# indication.net
KiCad netlist of a schematic drawn in EAGLE
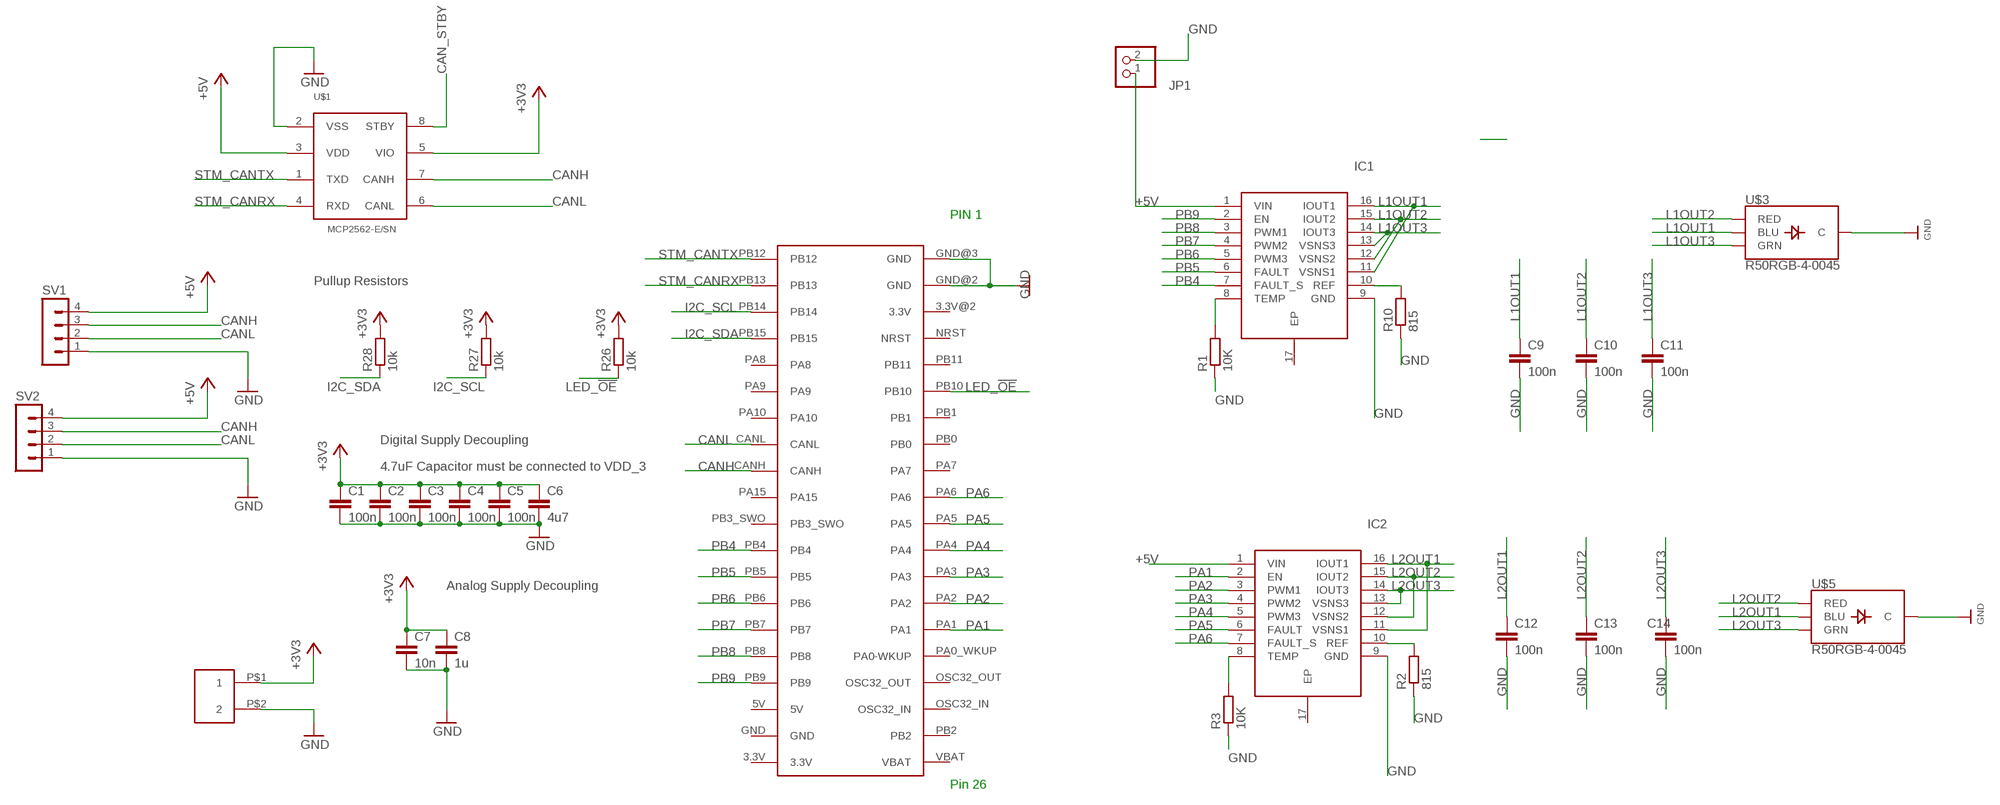
[diagram p0: schematic, sheet 1]

(export (version "E")
  (design (tool "Eeschema 10.0.6"))
  (components
    (comp (ref "C1")
      (value "100n")
      (footprint "eagle-import:C0805")
      (libsource (lib "eagle-import") (part "resistor_348_C-EUC0805"))
    )
    (comp (ref "C2")
      (value "100n")
      (footprint "eagle-import:C0805")
      (libsource (lib "eagle-import") (part "resistor_348_C-EUC0805"))
    )
    (comp (ref "C3")
      (value "100n")
      (footprint "eagle-import:C0805")
      (libsource (lib "eagle-import") (part "resistor_348_C-EUC0805"))
    )
    (comp (ref "C4")
      (value "100n")
      (footprint "eagle-import:C0805")
      (libsource (lib "eagle-import") (part "resistor_348_C-EUC0805"))
    )
    (comp (ref "C5")
      (value "100n")
      (footprint "eagle-import:C0805")
      (libsource (lib "eagle-import") (part "resistor_348_C-EUC0805"))
    )
    (comp (ref "C6")
      (value "4u7")
      (footprint "eagle-import:C0805")
      (libsource (lib "eagle-import") (part "resistor_348_C-EUC0805"))
    )
    (comp (ref "C7")
      (value "10n")
      (footprint "eagle-import:C0805")
      (libsource (lib "eagle-import") (part "resistor_348_C-EUC0805"))
    )
    (comp (ref "C8")
      (value "1u")
      (footprint "eagle-import:C0805")
      (libsource (lib "eagle-import") (part "resistor_348_C-EUC0805"))
    )
    (comp (ref "C9")
      (value "100n")
      (footprint "eagle-import:C0805")
      (libsource (lib "eagle-import") (part "C-EUC0805"))
    )
    (comp (ref "C10")
      (value "100n")
      (footprint "eagle-import:C0805")
      (libsource (lib "eagle-import") (part "C-EUC0805"))
    )
    (comp (ref "C11")
      (value "100n")
      (footprint "eagle-import:C0805")
      (libsource (lib "eagle-import") (part "C-EUC0805"))
    )
    (comp (ref "C12")
      (value "100n")
      (footprint "eagle-import:C0805")
      (libsource (lib "eagle-import") (part "C-EUC0805"))
    )
    (comp (ref "C13")
      (value "100n")
      (footprint "eagle-import:C0805")
      (libsource (lib "eagle-import") (part "C-EUC0805"))
    )
    (comp (ref "C14")
      (value "100n")
      (footprint "eagle-import:C0805")
      (libsource (lib "eagle-import") (part "C-EUC0805"))
    )
    (comp (ref "IC1")
      (value "TPS92630QPWPRQ1")
      (footprint "eagle-import:SOP65P640X120-17N")
      (fields (field (name "MOUSER_PART_NUMBER") "595-TPS92630QPWPRQ1"))
      (libsource (lib "eagle-import") (part "TPS92630QPWPRQ1"))
    )
    (comp (ref "IC2")
      (value "TPS92630QPWPRQ1")
      (footprint "eagle-import:SOP65P640X120-17N")
      (fields (field (name "MOUSER_PART_NUMBER") "595-TPS92630QPWPRQ1"))
      (libsource (lib "eagle-import") (part "TPS92630QPWPRQ1"))
    )
    (comp (ref "JP1")
      (value "PINHD-1X2")
      (footprint "eagle-import:1X02")
      (libsource (lib "eagle-import") (part "PINHD-1X2"))
    )
    (comp (ref "R1")
      (value "10K")
      (footprint "eagle-import:R0805")
      (libsource (lib "eagle-import") (part "R-EU_R0805"))
    )
    (comp (ref "R2")
      (value "815")
      (footprint "eagle-import:R0805")
      (libsource (lib "eagle-import") (part "R-EU_R0805"))
    )
    (comp (ref "R3")
      (value "10K")
      (footprint "eagle-import:R0805")
      (libsource (lib "eagle-import") (part "R-EU_R0805"))
    )
    (comp (ref "R10")
      (value "815")
      (footprint "eagle-import:R0805")
      (libsource (lib "eagle-import") (part "R-EU_R0805"))
    )
    (comp (ref "R26")
      (value "10k")
      (footprint "eagle-import:R0805")
      (libsource (lib "eagle-import") (part "R-EU_R0805"))
    )
    (comp (ref "R27")
      (value "10k")
      (footprint "eagle-import:R0805")
      (libsource (lib "eagle-import") (part "R-EU_R0805"))
    )
    (comp (ref "R28")
      (value "10k")
      (footprint "eagle-import:R0805")
      (libsource (lib "eagle-import") (part "R-EU_R0805"))
    )
    (comp (ref "SV1")
      (value "MA04-1")
      (footprint "eagle-import:MA04-1")
      (libsource (lib "eagle-import") (part "MA04-1"))
    )
    (comp (ref "SV2")
      (value "MA04-1")
      (footprint "eagle-import:MA04-1")
      (libsource (lib "eagle-import") (part "MA04-1"))
    )
    (comp (ref "U$1")
      (value "MCP2562-E/SN")
      (footprint "eagle-import:SOIC8")
      (libsource (lib "eagle-import") (part "MCP2562-E/SN"))
    )
    (comp (ref "U$2")
      (value "STM-DEV-BOARD")
      (footprint "eagle-import:STM-DEV-BOARD")
      (libsource (lib "eagle-import") (part "STM-DEV-BOARD"))
    )
    (comp (ref "U$3")
      (value "R50RGB-4-0045")
      (footprint "eagle-import:R50RGB-4-0045")
      (libsource (lib "eagle-import") (part "R50RGB-4-0045"))
    )
    (comp (ref "U$4")
      (value "TE-CONN_5-103669-1")
      (footprint "eagle-import:TE-CONN_5-103669-1")
      (libsource (lib "eagle-import") (part "TE-CONN_5-103669-1"))
    )
    (comp (ref "U$5")
      (value "R50RGB-4-0045")
      (footprint "eagle-import:R50RGB-4-0045")
      (libsource (lib "eagle-import") (part "R50RGB-4-0045"))
    )
  )
  (nets
    (net (code "1") (name "+3V3") (class "Default")
      (node (ref "C1") (pin "1") (pinfunction "1_1") (pintype "passive"))
      (node (ref "C2") (pin "1") (pinfunction "1_1") (pintype "passive"))
      (node (ref "C3") (pin "1") (pinfunction "1_1") (pintype "passive"))
      (node (ref "C4") (pin "1") (pinfunction "1_1") (pintype "passive"))
      (node (ref "C5") (pin "1") (pinfunction "1_1") (pintype "passive"))
      (node (ref "C6") (pin "1") (pinfunction "1_1") (pintype "passive"))
      (node (ref "C7") (pin "1") (pinfunction "1_1") (pintype "passive"))
      (node (ref "C8") (pin "1") (pinfunction "1_1") (pintype "passive"))
      (node (ref "R26") (pin "2") (pinfunction "2_2") (pintype "passive"))
      (node (ref "R27") (pin "2") (pinfunction "2_2") (pintype "passive"))
      (node (ref "R28") (pin "2") (pinfunction "2_2") (pintype "passive"))
      (node (ref "U$1") (pin "5") (pinfunction "VIO_5") (pintype "bidirectional"))
      (node (ref "U$4") (pin "P$1") (pinfunction "1_P$1") (pintype "bidirectional"))
    )
    (net (code "2") (name "+5V") (class "Default")
      (node (ref "IC1") (pin "1") (pinfunction "VIN_1") (pintype "bidirectional"))
      (node (ref "IC2") (pin "1") (pinfunction "VIN_1") (pintype "bidirectional"))
      (node (ref "JP1") (pin "1") (pinfunction "1_1") (pintype "passive"))
      (node (ref "SV1") (pin "4") (pinfunction "4_4") (pintype "passive"))
      (node (ref "SV2") (pin "4") (pinfunction "4_4") (pintype "passive"))
      (node (ref "U$1") (pin "3") (pinfunction "VDD_3") (pintype "bidirectional"))
    )
    (net (code "3") (name "/CANH") (class "Default")
      (node (ref "SV1") (pin "3") (pinfunction "3_3") (pintype "passive"))
      (node (ref "SV2") (pin "3") (pinfunction "3_3") (pintype "passive"))
      (node (ref "U$1") (pin "7") (pinfunction "CANH_7") (pintype "bidirectional"))
      (node (ref "U$2") (pin "CANH") (pinfunction "CANH_CANH") (pintype "bidirectional"))
    )
    (net (code "4") (name "/CANL") (class "Default")
      (node (ref "SV1") (pin "2") (pinfunction "2_2") (pintype "passive"))
      (node (ref "SV2") (pin "2") (pinfunction "2_2") (pintype "passive"))
      (node (ref "U$1") (pin "6") (pinfunction "CANL_6") (pintype "bidirectional"))
      (node (ref "U$2") (pin "CANL") (pinfunction "CANL_CANL") (pintype "bidirectional"))
    )
    (net (code "5") (name "/CAN_STBY") (class "Default")
      (node (ref "U$1") (pin "8") (pinfunction "STBY_8") (pintype "bidirectional"))
    )
    (net (code "6") (name "/I2C_SCL") (class "Default")
      (node (ref "R27") (pin "1") (pinfunction "1_1") (pintype "passive"))
      (node (ref "U$2") (pin "PB14") (pinfunction "PB14_PB14") (pintype "bidirectional"))
    )
    (net (code "7") (name "/I2C_SDA") (class "Default")
      (node (ref "R28") (pin "1") (pinfunction "1_1") (pintype "passive"))
      (node (ref "U$2") (pin "PB15") (pinfunction "PB15_PB15") (pintype "bidirectional"))
    )
    (net (code "8") (name "/L1OUT1") (class "Default")
      (node (ref "C9") (pin "1") (pinfunction "1_1") (pintype "passive"))
      (node (ref "IC1") (pin "11") (pinfunction "VSNS1_11") (pintype "bidirectional"))
      (node (ref "IC1") (pin "16") (pinfunction "IOUT1_16") (pintype "bidirectional"))
      (node (ref "U$3") (pin "P$3") (pinfunction "BLU_P$3") (pintype "bidirectional"))
    )
    (net (code "9") (name "/L1OUT2") (class "Default")
      (node (ref "C10") (pin "1") (pinfunction "1_1") (pintype "passive"))
      (node (ref "IC1") (pin "12") (pinfunction "VSNS2_12") (pintype "bidirectional"))
      (node (ref "IC1") (pin "15") (pinfunction "IOUT2_15") (pintype "bidirectional"))
      (node (ref "U$3") (pin "P$4") (pinfunction "RED_P$4") (pintype "bidirectional"))
    )
    (net (code "10") (name "/L1OUT3") (class "Default")
      (node (ref "C11") (pin "1") (pinfunction "1_1") (pintype "passive"))
      (node (ref "IC1") (pin "13") (pinfunction "VSNS3_13") (pintype "bidirectional"))
      (node (ref "IC1") (pin "14") (pinfunction "IOUT3_14") (pintype "bidirectional"))
      (node (ref "U$3") (pin "P$1") (pinfunction "GRN_P$1") (pintype "bidirectional"))
    )
    (net (code "11") (name "/L2OUT1") (class "Default")
      (node (ref "C12") (pin "1") (pinfunction "1_1") (pintype "passive"))
      (node (ref "IC2") (pin "11") (pinfunction "VSNS1_11") (pintype "bidirectional"))
      (node (ref "IC2") (pin "16") (pinfunction "IOUT1_16") (pintype "bidirectional"))
      (node (ref "U$5") (pin "P$3") (pinfunction "BLU_P$3") (pintype "bidirectional"))
    )
    (net (code "12") (name "/L2OUT2") (class "Default")
      (node (ref "C13") (pin "1") (pinfunction "1_1") (pintype "passive"))
      (node (ref "IC2") (pin "12") (pinfunction "VSNS2_12") (pintype "bidirectional"))
      (node (ref "IC2") (pin "15") (pinfunction "IOUT2_15") (pintype "bidirectional"))
      (node (ref "U$5") (pin "P$4") (pinfunction "RED_P$4") (pintype "bidirectional"))
    )
    (net (code "13") (name "/L2OUT3") (class "Default")
      (node (ref "C14") (pin "1") (pinfunction "1_1") (pintype "passive"))
      (node (ref "IC2") (pin "13") (pinfunction "VSNS3_13") (pintype "bidirectional"))
      (node (ref "IC2") (pin "14") (pinfunction "IOUT3_14") (pintype "bidirectional"))
      (node (ref "U$5") (pin "P$1") (pinfunction "GRN_P$1") (pintype "bidirectional"))
    )
    (net (code "14") (name "/LED_~{OE}") (class "Default")
      (node (ref "R26") (pin "1") (pinfunction "1_1") (pintype "passive"))
      (node (ref "U$2") (pin "PB10") (pinfunction "PB10_PB10") (pintype "bidirectional"))
    )
    (net (code "15") (name "/PA1") (class "Default")
      (node (ref "IC2") (pin "2") (pinfunction "EN_2") (pintype "bidirectional"))
      (node (ref "U$2") (pin "PA1") (pinfunction "PA1_PA1") (pintype "bidirectional"))
    )
    (net (code "16") (name "/PA2") (class "Default")
      (node (ref "IC2") (pin "3") (pinfunction "PWM1_3") (pintype "bidirectional"))
      (node (ref "U$2") (pin "PA2") (pinfunction "PA2_PA2") (pintype "bidirectional"))
    )
    (net (code "17") (name "/PA3") (class "Default")
      (node (ref "IC2") (pin "4") (pinfunction "PWM2_4") (pintype "bidirectional"))
      (node (ref "U$2") (pin "PA3") (pinfunction "PA3_PA3") (pintype "bidirectional"))
    )
    (net (code "18") (name "/PA4") (class "Default")
      (node (ref "IC2") (pin "5") (pinfunction "PWM3_5") (pintype "bidirectional"))
      (node (ref "U$2") (pin "PA4") (pinfunction "PA4_PA4") (pintype "bidirectional"))
    )
    (net (code "19") (name "/PA5") (class "Default")
      (node (ref "IC2") (pin "6") (pinfunction "FAULT_6") (pintype "bidirectional"))
      (node (ref "U$2") (pin "PA5") (pinfunction "PA5_PA5") (pintype "bidirectional"))
    )
    (net (code "20") (name "/PA6") (class "Default")
      (node (ref "IC2") (pin "7") (pinfunction "FAULT_S_7") (pintype "bidirectional"))
      (node (ref "U$2") (pin "PA6") (pinfunction "PA6_PA6") (pintype "bidirectional"))
    )
    (net (code "21") (name "/PB4") (class "Default")
      (node (ref "IC1") (pin "7") (pinfunction "FAULT_S_7") (pintype "bidirectional"))
      (node (ref "U$2") (pin "PB4") (pinfunction "PB4_PB4") (pintype "bidirectional"))
    )
    (net (code "22") (name "/PB5") (class "Default")
      (node (ref "IC1") (pin "6") (pinfunction "FAULT_6") (pintype "bidirectional"))
      (node (ref "U$2") (pin "PB5") (pinfunction "PB5_PB5") (pintype "bidirectional"))
    )
    (net (code "23") (name "/PB6") (class "Default")
      (node (ref "IC1") (pin "5") (pinfunction "PWM3_5") (pintype "bidirectional"))
      (node (ref "U$2") (pin "PB6") (pinfunction "PB6_PB6") (pintype "bidirectional"))
    )
    (net (code "24") (name "/PB7") (class "Default")
      (node (ref "IC1") (pin "4") (pinfunction "PWM2_4") (pintype "bidirectional"))
      (node (ref "U$2") (pin "PB7") (pinfunction "PB7_PB7") (pintype "bidirectional"))
    )
    (net (code "25") (name "/PB8") (class "Default")
      (node (ref "IC1") (pin "3") (pinfunction "PWM1_3") (pintype "bidirectional"))
      (node (ref "U$2") (pin "PB8") (pinfunction "PB8_PB8") (pintype "bidirectional"))
    )
    (net (code "26") (name "/PB9") (class "Default")
      (node (ref "IC1") (pin "2") (pinfunction "EN_2") (pintype "bidirectional"))
      (node (ref "U$2") (pin "PB9") (pinfunction "PB9_PB9") (pintype "bidirectional"))
    )
    (net (code "27") (name "/STM_CANRX") (class "Default")
      (node (ref "U$1") (pin "4") (pinfunction "RXD_4") (pintype "bidirectional"))
      (node (ref "U$2") (pin "PB13") (pinfunction "PB13_PB13") (pintype "bidirectional"))
    )
    (net (code "28") (name "/STM_CANTX") (class "Default")
      (node (ref "U$1") (pin "1") (pinfunction "TXD_1") (pintype "bidirectional"))
      (node (ref "U$2") (pin "PB12") (pinfunction "PB12_PB12") (pintype "bidirectional"))
    )
    (net (code "29") (name "GND") (class "Default")
      (node (ref "C1") (pin "2") (pinfunction "2_2") (pintype "passive"))
      (node (ref "C10") (pin "2") (pinfunction "2_2") (pintype "passive"))
      (node (ref "C11") (pin "2") (pinfunction "2_2") (pintype "passive"))
      (node (ref "C12") (pin "2") (pinfunction "2_2") (pintype "passive"))
      (node (ref "C13") (pin "2") (pinfunction "2_2") (pintype "passive"))
      (node (ref "C14") (pin "2") (pinfunction "2_2") (pintype "passive"))
      (node (ref "C2") (pin "2") (pinfunction "2_2") (pintype "passive"))
      (node (ref "C3") (pin "2") (pinfunction "2_2") (pintype "passive"))
      (node (ref "C4") (pin "2") (pinfunction "2_2") (pintype "passive"))
      (node (ref "C5") (pin "2") (pinfunction "2_2") (pintype "passive"))
      (node (ref "C6") (pin "2") (pinfunction "2_2") (pintype "passive"))
      (node (ref "C7") (pin "2") (pinfunction "2_2") (pintype "passive"))
      (node (ref "C8") (pin "2") (pinfunction "2_2") (pintype "passive"))
      (node (ref "C9") (pin "2") (pinfunction "2_2") (pintype "passive"))
      (node (ref "IC1") (pin "9") (pinfunction "GND_9") (pintype "bidirectional"))
      (node (ref "IC2") (pin "9") (pinfunction "GND_9") (pintype "bidirectional"))
      (node (ref "JP1") (pin "2") (pinfunction "2_2") (pintype "passive"))
      (node (ref "R1") (pin "1") (pinfunction "1_1") (pintype "passive"))
      (node (ref "R10") (pin "1") (pinfunction "1_1") (pintype "passive"))
      (node (ref "R2") (pin "1") (pinfunction "1_1") (pintype "passive"))
      (node (ref "R3") (pin "1") (pinfunction "1_1") (pintype "passive"))
      (node (ref "SV1") (pin "1") (pinfunction "1_1") (pintype "passive"))
      (node (ref "SV2") (pin "1") (pinfunction "1_1") (pintype "passive"))
      (node (ref "U$1") (pin "2") (pinfunction "VSS_2") (pintype "bidirectional"))
      (node (ref "U$2") (pin "GND@2") (pinfunction "GND_GND@2") (pintype "bidirectional"))
      (node (ref "U$2") (pin "GND@3") (pinfunction "GND_GND@3") (pintype "bidirectional"))
      (node (ref "U$3") (pin "P$2") (pinfunction "C_P$2") (pintype "bidirectional"))
      (node (ref "U$4") (pin "P$2") (pinfunction "2_P$2") (pintype "bidirectional"))
      (node (ref "U$5") (pin "P$2") (pinfunction "C_P$2") (pintype "bidirectional"))
    )
    (net (code "30") (name "Net-(IC1-REF)") (class "Default")
      (node (ref "IC1") (pin "10") (pinfunction "REF_10") (pintype "bidirectional"))
      (node (ref "R10") (pin "2") (pinfunction "2_2") (pintype "passive"))
    )
    (net (code "31") (name "Net-(IC1-TEMP)") (class "Default")
      (node (ref "IC1") (pin "8") (pinfunction "TEMP_8") (pintype "bidirectional"))
      (node (ref "R1") (pin "2") (pinfunction "2_2") (pintype "passive"))
    )
    (net (code "32") (name "Net-(IC2-REF)") (class "Default")
      (node (ref "IC2") (pin "10") (pinfunction "REF_10") (pintype "bidirectional"))
      (node (ref "R2") (pin "2") (pinfunction "2_2") (pintype "passive"))
    )
    (net (code "33") (name "Net-(IC2-TEMP)") (class "Default")
      (node (ref "IC2") (pin "8") (pinfunction "TEMP_8") (pintype "bidirectional"))
      (node (ref "R3") (pin "2") (pinfunction "2_2") (pintype "passive"))
    )
    (net (code "34") (name "unconnected-(IC1-EP-Pad17)") (class "Default")
      (node (ref "IC1") (pin "17") (pinfunction "EP_17") (pintype "bidirectional"))
    )
    (net (code "35") (name "unconnected-(IC2-EP-Pad17)") (class "Default")
      (node (ref "IC2") (pin "17") (pinfunction "EP_17") (pintype "bidirectional"))
    )
    (net (code "36") (name "unconnected-(U$2-3.3V-Pad3.3V@2)") (class "Default")
      (node (ref "U$2") (pin "3.3V@2") (pinfunction "3.3V_3.3V@2") (pintype "bidirectional"))
    )
    (net (code "37") (name "unconnected-(U$2-PA0-WKUP-PadPA0_WKUP)") (class "Default")
      (node (ref "U$2") (pin "PA0_WKUP") (pinfunction "PA0-WKUP_PA0_WKUP") (pintype "bidirectional"))
    )
    (net (code "38") (name "unconnected-(U$2-Pad3.3V)") (class "Default")
      (node (ref "U$2") (pin "3.3V") (pinfunction "3.3V_3.3V") (pintype "bidirectional"))
    )
    (net (code "39") (name "unconnected-(U$2-Pad5V)") (class "Default")
      (node (ref "U$2") (pin "5V") (pinfunction "5V_5V") (pintype "bidirectional"))
    )
    (net (code "40") (name "unconnected-(U$2-PadGND)") (class "Default")
      (node (ref "U$2") (pin "GND") (pinfunction "GND_GND") (pintype "bidirectional"))
    )
    (net (code "41") (name "unconnected-(U$2-PadNRST)") (class "Default")
      (node (ref "U$2") (pin "NRST") (pinfunction "NRST_NRST") (pintype "bidirectional"))
    )
    (net (code "42") (name "unconnected-(U$2-PadOSC32_IN)") (class "Default")
      (node (ref "U$2") (pin "OSC32_IN") (pinfunction "OSC32_IN_OSC32_IN") (pintype "bidirectional"))
    )
    (net (code "43") (name "unconnected-(U$2-PadOSC32_OUT)") (class "Default")
      (node (ref "U$2") (pin "OSC32_OUT") (pinfunction "OSC32_OUT_OSC32_OUT") (pintype "bidirectional"))
    )
    (net (code "44") (name "unconnected-(U$2-PadPA7)") (class "Default")
      (node (ref "U$2") (pin "PA7") (pinfunction "PA7_PA7") (pintype "bidirectional"))
    )
    (net (code "45") (name "unconnected-(U$2-PadPA8)") (class "Default")
      (node (ref "U$2") (pin "PA8") (pinfunction "PA8_PA8") (pintype "bidirectional"))
    )
    (net (code "46") (name "unconnected-(U$2-PadPA9)") (class "Default")
      (node (ref "U$2") (pin "PA9") (pinfunction "PA9_PA9") (pintype "bidirectional"))
    )
    (net (code "47") (name "unconnected-(U$2-PadPA10)") (class "Default")
      (node (ref "U$2") (pin "PA10") (pinfunction "PA10_PA10") (pintype "bidirectional"))
    )
    (net (code "48") (name "unconnected-(U$2-PadPA15)") (class "Default")
      (node (ref "U$2") (pin "PA15") (pinfunction "PA15_PA15") (pintype "bidirectional"))
    )
    (net (code "49") (name "unconnected-(U$2-PadPB0)") (class "Default")
      (node (ref "U$2") (pin "PB0") (pinfunction "PB0_PB0") (pintype "bidirectional"))
    )
    (net (code "50") (name "unconnected-(U$2-PadPB1)") (class "Default")
      (node (ref "U$2") (pin "PB1") (pinfunction "PB1_PB1") (pintype "bidirectional"))
    )
    (net (code "51") (name "unconnected-(U$2-PadPB2)") (class "Default")
      (node (ref "U$2") (pin "PB2") (pinfunction "PB2_PB2") (pintype "bidirectional"))
    )
    (net (code "52") (name "unconnected-(U$2-PadPB3_SWO)") (class "Default")
      (node (ref "U$2") (pin "PB3_SWO") (pinfunction "PB3_SWO_PB3_SWO") (pintype "bidirectional"))
    )
    (net (code "53") (name "unconnected-(U$2-PadPB11)") (class "Default")
      (node (ref "U$2") (pin "PB11") (pinfunction "PB11_PB11") (pintype "bidirectional"))
    )
    (net (code "54") (name "unconnected-(U$2-PadVBAT)") (class "Default")
      (node (ref "U$2") (pin "VBAT") (pinfunction "VBAT_VBAT") (pintype "bidirectional"))
    )
  )
)
